# photon_at7020_1.net
KiCad netlist of a schematic drawn in EAGLE
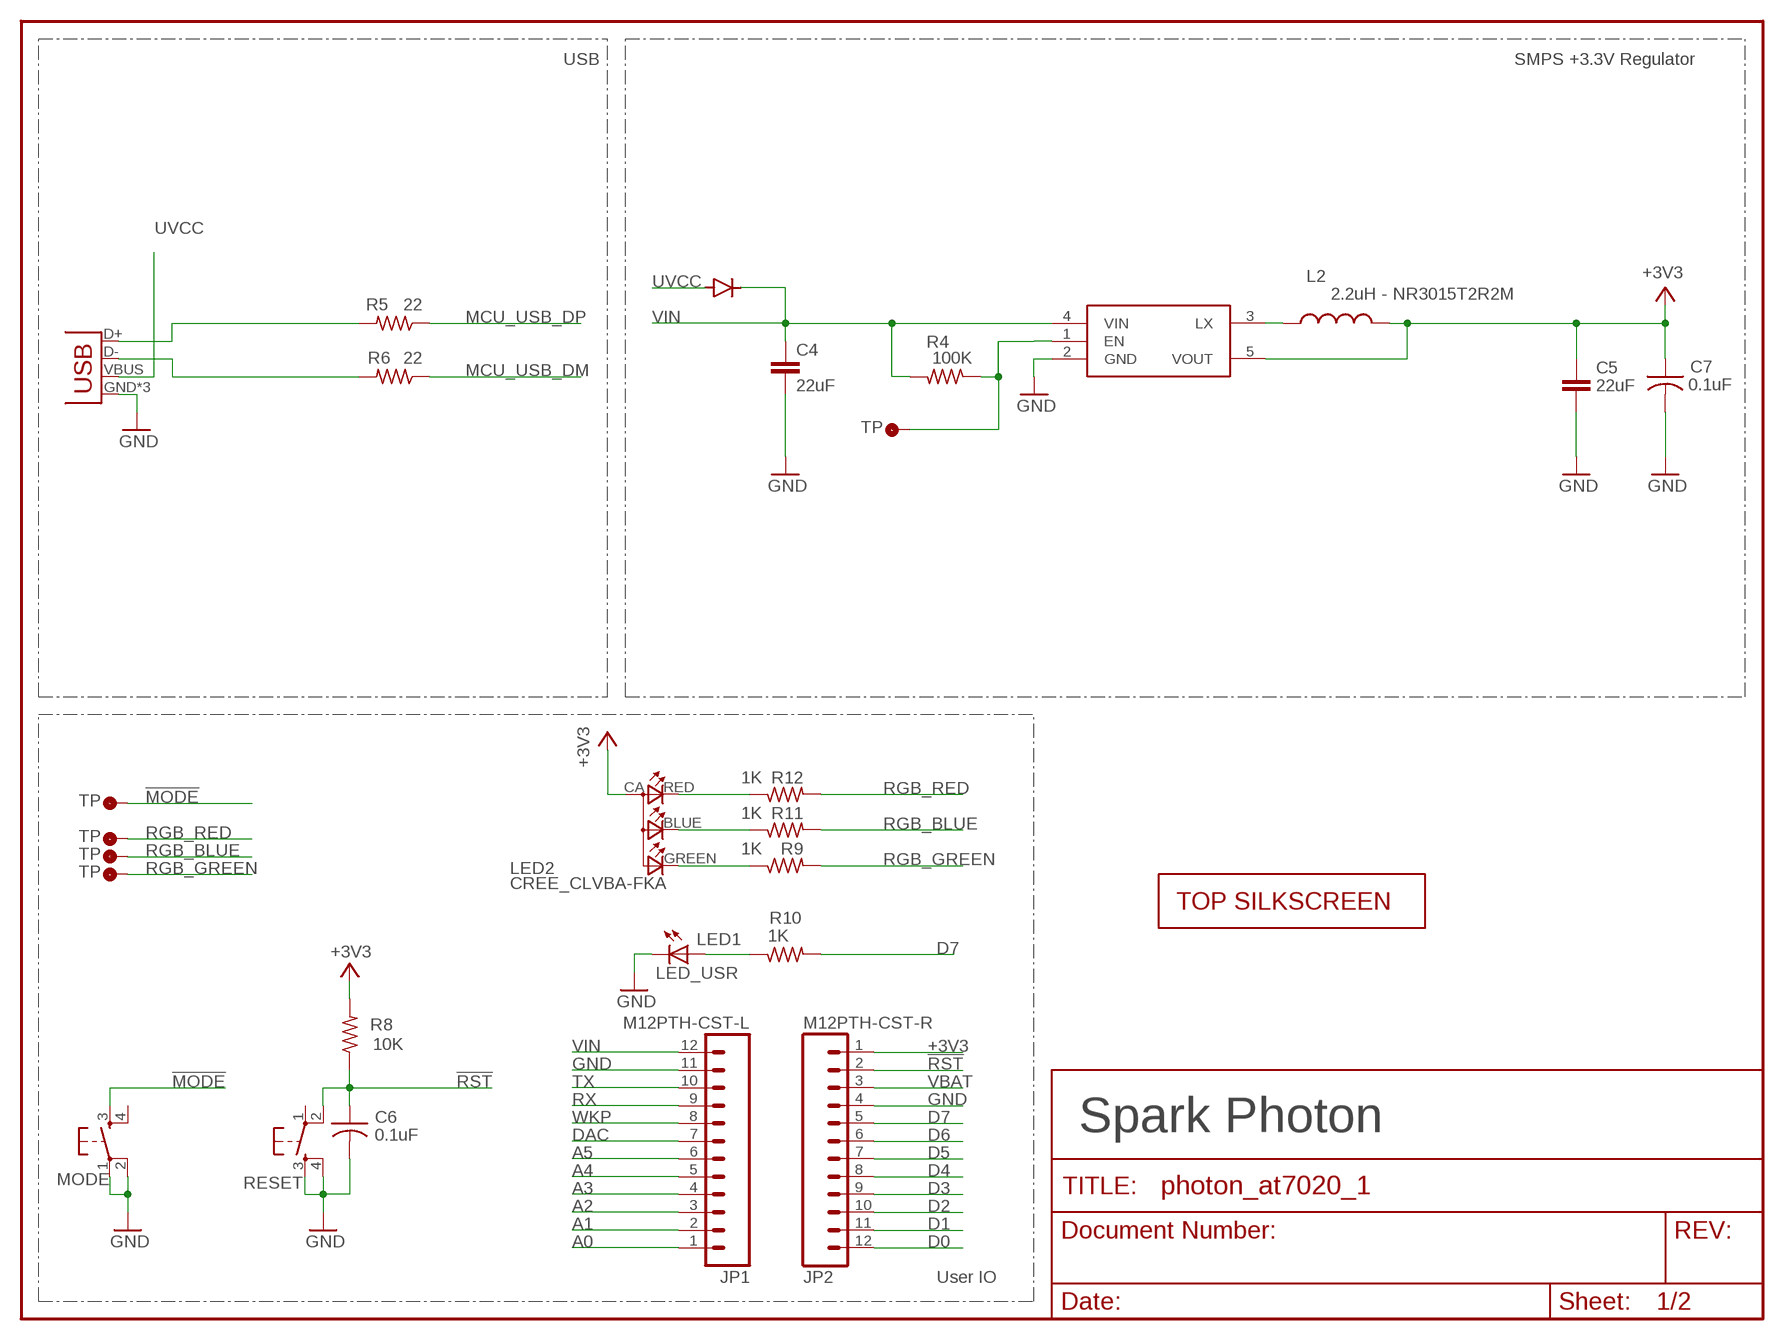
[diagram p0: schematic, sheet 1]
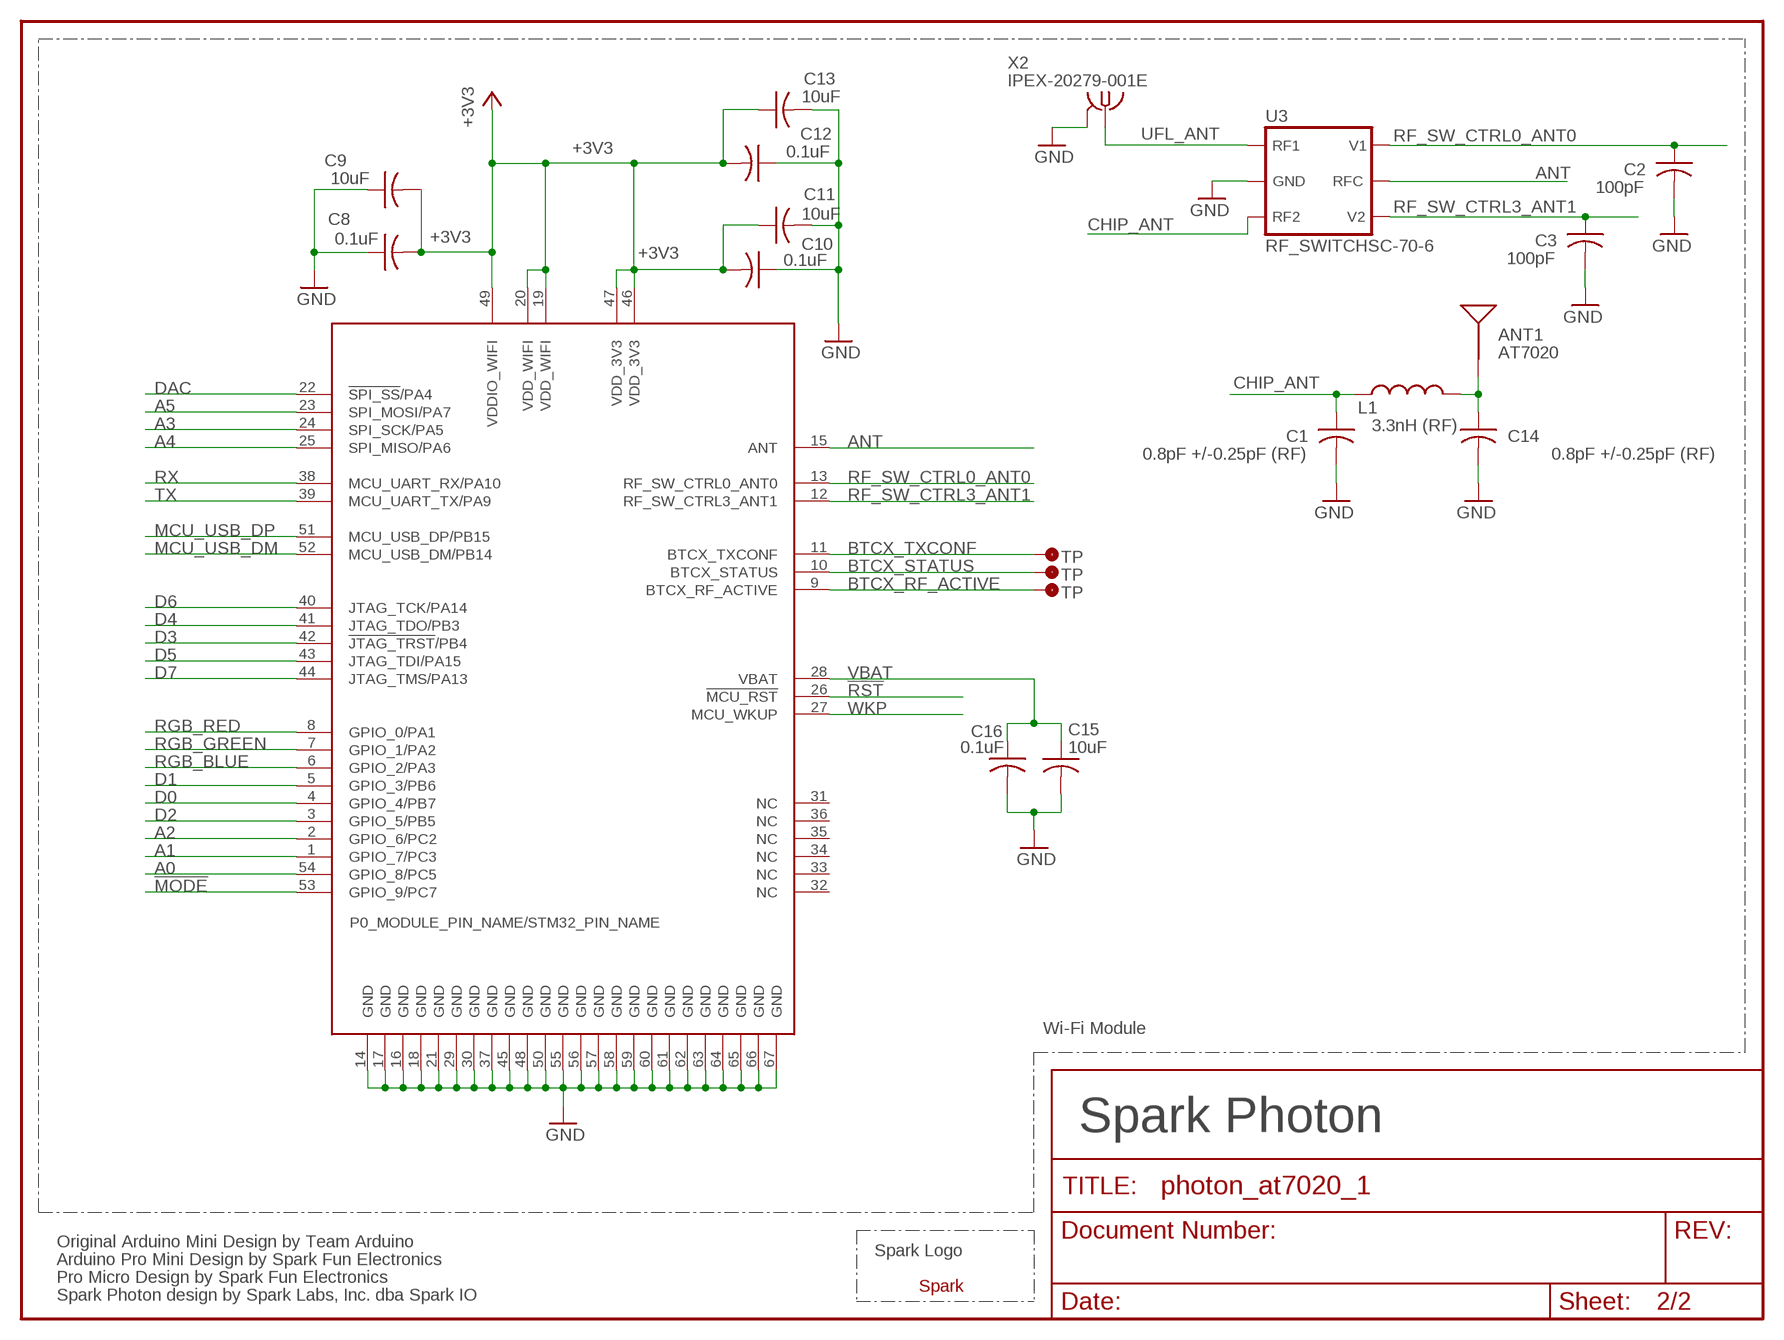
[diagram p1: schematic, sheet 2]

(export (version "E")
  (design (tool "Eeschema 10.0.6"))
  (components
    (comp (ref "C4")
      (value "22uF")
      (footprint "eagle-import:C0603")
      (libsource (lib "eagle-import") (part "C-EUC0603"))
    )
    (comp (ref "C5")
      (value "22uF")
      (footprint "eagle-import:C0603")
      (libsource (lib "eagle-import") (part "C-EUC0603"))
    )
    (comp (ref "C6")
      (value "0.1uF")
      (footprint "eagle-import:C0402_B")
      (libsource (lib "eagle-import") (part "C-US"))
    )
    (comp (ref "C7")
      (value "0.1uF")
      (footprint "eagle-import:C0402")
      (libsource (lib "eagle-import") (part "C-USC0402"))
    )
    (comp (ref "D1")
      (value "DIODE")
      (footprint "eagle-import:DIODE-DO-220AA(SMP)")
      (libsource (lib "eagle-import") (part "DIODE"))
    )
    (comp (ref "JP1")
      (value "M12PTH-CST-L")
      (footprint "eagle-import:1X12-CASTELLATED")
      (libsource (lib "eagle-import") (part "M12PTH-CST-L"))
    )
    (comp (ref "JP2")
      (value "M12PTH-CST-R")
      (footprint "eagle-import:1X12-CASTELLATED")
      (libsource (lib "eagle-import") (part "M12PTH-CST-R"))
    )
    (comp (ref "L2")
      (value "2.2uH - NR3015T2R2M")
      (footprint "eagle-import:INDUCTOR-NR3015")
      (libsource (lib "eagle-import") (part "INDUCTORB"))
    )
    (comp (ref "LED2")
      (value "CREE_CLVBA-FKA")
      (footprint "eagle-import:PLCC4-2MM-RGB")
      (libsource (lib "eagle-import") (part "RGB-LED-CLMVB-FKARGB"))
    )
    (comp (ref "LED_USR")
      (value "LED0603")
      (footprint "eagle-import:LED-0603")
      (libsource (lib "eagle-import") (part "LED0603"))
    )
    (comp (ref "MODE")
      (value "KMR211GLFS")
      (footprint "eagle-import:TACTILE_SWITCH_SMD")
      (libsource (lib "eagle-import") (part "TAC_SWITCHSMD"))
    )
    (comp (ref "R4")
      (value "100K")
      (footprint "eagle-import:R0402_B")
      (libsource (lib "eagle-import") (part "R-US_"))
    )
    (comp (ref "R5")
      (value "22")
      (footprint "eagle-import:R0402_B")
      (libsource (lib "eagle-import") (part "R-US_"))
    )
    (comp (ref "R6")
      (value "22")
      (footprint "eagle-import:R0402_B")
      (libsource (lib "eagle-import") (part "R-US_"))
    )
    (comp (ref "R8")
      (value "10K")
      (footprint "eagle-import:R0402_B")
      (libsource (lib "eagle-import") (part "R-US_"))
    )
    (comp (ref "R9")
      (value "1K")
      (footprint "eagle-import:R0402_B")
      (libsource (lib "eagle-import") (part "R-US_"))
    )
    (comp (ref "R10")
      (value "1K")
      (footprint "eagle-import:R0402_B")
      (libsource (lib "eagle-import") (part "R-US_"))
    )
    (comp (ref "R11")
      (value "1K")
      (footprint "eagle-import:R0402_B")
      (libsource (lib "eagle-import") (part "R-US_"))
    )
    (comp (ref "R12")
      (value "1K")
      (footprint "eagle-import:R0402_B")
      (libsource (lib "eagle-import") (part "R-US_"))
    )
    (comp (ref "RESET")
      (value "KMR211GLFS")
      (footprint "eagle-import:TACTILE_SWITCH_SMD")
      (libsource (lib "eagle-import") (part "TAC_SWITCHSMD"))
    )
    (comp (ref "U$1")
      (value "PHOTON-TOP-SS")
      (footprint "eagle-import:PHOTON-TOP-SS")
      (libsource (lib "eagle-import") (part "PHOTON-TOP-SS"))
    )
    (comp (ref "U$3")
      (value "TP1")
      (footprint "eagle-import:TP35_BOT")
      (libsource (lib "eagle-import") (part "TP1"))
    )
    (comp (ref "U$5")
      (value "TP1")
      (footprint "eagle-import:TP35_BOT")
      (libsource (lib "eagle-import") (part "TP1"))
    )
    (comp (ref "U$6")
      (value "TP1")
      (footprint "eagle-import:TP35_BOT")
      (libsource (lib "eagle-import") (part "TP1"))
    )
    (comp (ref "U$7")
      (value "TP1")
      (footprint "eagle-import:TP35_BOT")
      (libsource (lib "eagle-import") (part "TP1"))
    )
    (comp (ref "U$11")
      (value "R8008-33")
      (footprint "eagle-import:SOT23-5")
      (libsource (lib "eagle-import") (part "R8008-33"))
    )
    (comp (ref "U$12")
      (value "TP1")
      (footprint "eagle-import:TP35_BOT")
      (libsource (lib "eagle-import") (part "TP1"))
    )
    (comp (ref "X1")
      (value "USB-MICROB")
      (footprint "eagle-import:USB-MICROB-SLOT-HOLE")
      (libsource (lib "eagle-import") (part "USBUSB-MICROB-SLOT-HOLE"))
    )
    (comp (ref "ANT1")
      (value "AT7020")
      (footprint "eagle-import:AT7020")
      (libsource (lib "eagle-import") (part "AT7020"))
    )
    (comp (ref "C1")
      (value "0.8pF +/-0.25pF (RF)")
      (footprint "eagle-import:C0402_B")
      (libsource (lib "eagle-import") (part "C-US"))
    )
    (comp (ref "C2")
      (value "100pF")
      (footprint "eagle-import:C0402_B")
      (libsource (lib "eagle-import") (part "C-US"))
    )
    (comp (ref "C3")
      (value "100pF")
      (footprint "eagle-import:C0402_B")
      (libsource (lib "eagle-import") (part "C-US"))
    )
    (comp (ref "C8")
      (value "0.1uF")
      (footprint "eagle-import:C0402_B")
      (libsource (lib "eagle-import") (part "C-US"))
    )
    (comp (ref "C9")
      (value "10uF")
      (footprint "eagle-import:C0402_B")
      (libsource (lib "eagle-import") (part "C-US"))
    )
    (comp (ref "C10")
      (value "0.1uF")
      (footprint "eagle-import:C0402_B")
      (libsource (lib "eagle-import") (part "C-US"))
    )
    (comp (ref "C11")
      (value "10uF")
      (footprint "eagle-import:C0402_B")
      (libsource (lib "eagle-import") (part "C-US"))
    )
    (comp (ref "C12")
      (value "0.1uF")
      (footprint "eagle-import:C0402_B")
      (libsource (lib "eagle-import") (part "C-US"))
    )
    (comp (ref "C13")
      (value "10uF")
      (footprint "eagle-import:C0402_B")
      (libsource (lib "eagle-import") (part "C-US"))
    )
    (comp (ref "C14")
      (value "0.8pF +/-0.25pF (RF)")
      (footprint "eagle-import:C0402_B")
      (libsource (lib "eagle-import") (part "C-US"))
    )
    (comp (ref "C15")
      (value "10uF")
      (footprint "eagle-import:C0402_B")
      (libsource (lib "eagle-import") (part "C-US"))
    )
    (comp (ref "C16")
      (value "0.1uF")
      (footprint "eagle-import:C0402_B")
      (libsource (lib "eagle-import") (part "C-US"))
    )
    (comp (ref "L1")
      (value "3.3nH (RF)")
      (footprint "eagle-import:L0402_B")
      (libsource (lib "eagle-import") (part "INDUCTOR"))
    )
    (comp (ref "U$2")
      (value "SPARK_LOGO2")
      (footprint "eagle-import:SPARK_LOGO2")
      (libsource (lib "eagle-import") (part "SPARK_LOGO2"))
    )
    (comp (ref "U$8")
      (value "TP1")
      (footprint "eagle-import:TP35_BOT")
      (libsource (lib "eagle-import") (part "TP1"))
    )
    (comp (ref "U$9")
      (value "TP1")
      (footprint "eagle-import:TP35_BOT")
      (libsource (lib "eagle-import") (part "TP1"))
    )
    (comp (ref "U$10")
      (value "TP1")
      (footprint "eagle-import:TP35_BOT")
      (libsource (lib "eagle-import") (part "TP1"))
    )
    (comp (ref "U1")
      (value "WM-N-BM-09")
      (footprint "eagle-import:WM-N-BM-09")
      (libsource (lib "eagle-import") (part "WM-N-BM-09"))
    )
    (comp (ref "U3")
      (value "RF_SWITCHSC-70-6")
      (footprint "eagle-import:SC70-6")
      (libsource (lib "eagle-import") (part "RF_SWITCHSC-70-6"))
    )
    (comp (ref "X2")
      (value "IPEX-20279-001E")
      (footprint "eagle-import:IPEX-20279-001E")
      (libsource (lib "eagle-import") (part "IPEX-20279-001E"))
    )
  )
  (nets
    (net (code "1") (name "+3V3") (class "Default")
      (node (ref "C10") (pin "2") (pinfunction "2_2") (pintype "passive"))
      (node (ref "C11") (pin "1") (pinfunction "1_1") (pintype "passive"))
      (node (ref "C12") (pin "2") (pinfunction "2_2") (pintype "passive"))
      (node (ref "C13") (pin "1") (pinfunction "1_1") (pintype "passive"))
      (node (ref "C5") (pin "1") (pinfunction "1_1") (pintype "passive"))
      (node (ref "C7") (pin "1") (pinfunction "1_1") (pintype "passive"))
      (node (ref "C8") (pin "2") (pinfunction "2_2") (pintype "passive"))
      (node (ref "C9") (pin "2") (pinfunction "2_2") (pintype "passive"))
      (node (ref "JP2") (pin "1") (pinfunction "1_1") (pintype "passive"))
      (node (ref "L2") (pin "2") (pinfunction "2_2") (pintype "passive"))
      (node (ref "LED2") (pin "CA") (pinfunction "A2_CA") (pintype "passive"))
      (node (ref "R8") (pin "2") (pinfunction "2_2") (pintype "passive"))
      (node (ref "U$11") (pin "5") (pinfunction "VOUT_5") (pintype "bidirectional"))
      (node (ref "U1") (pin "19") (pinfunction "VDD_WIFI_19") (pintype "bidirectional"))
      (node (ref "U1") (pin "20") (pinfunction "VDD_WIFI_20") (pintype "bidirectional"))
      (node (ref "U1") (pin "46") (pinfunction "VDD_3V3_46") (pintype "bidirectional"))
      (node (ref "U1") (pin "47") (pinfunction "VDD_3V3_47") (pintype "bidirectional"))
      (node (ref "U1") (pin "49") (pinfunction "VDDIO_WIFI_49") (pintype "bidirectional"))
    )
    (net (code "2") (name "A0") (class "Default")
      (node (ref "JP1") (pin "1") (pinfunction "12_1") (pintype "passive"))
      (node (ref "U1") (pin "54") (pinfunction "GPIO_8/PC5_54") (pintype "bidirectional"))
    )
    (net (code "3") (name "A1") (class "Default")
      (node (ref "JP1") (pin "2") (pinfunction "11_2") (pintype "passive"))
      (node (ref "U1") (pin "1") (pinfunction "GPIO_7/PC3_1") (pintype "bidirectional"))
    )
    (net (code "4") (name "A2") (class "Default")
      (node (ref "JP1") (pin "3") (pinfunction "10_3") (pintype "passive"))
      (node (ref "U1") (pin "2") (pinfunction "GPIO_6/PC2_2") (pintype "bidirectional"))
    )
    (net (code "5") (name "A3") (class "Default")
      (node (ref "JP1") (pin "4") (pinfunction "9_4") (pintype "passive"))
      (node (ref "U1") (pin "24") (pinfunction "SPI_SCK/PA5_24") (pintype "bidirectional"))
    )
    (net (code "6") (name "A4") (class "Default")
      (node (ref "JP1") (pin "5") (pinfunction "8_5") (pintype "passive"))
      (node (ref "U1") (pin "25") (pinfunction "SPI_MISO/PA6_25") (pintype "bidirectional"))
    )
    (net (code "7") (name "A5") (class "Default")
      (node (ref "JP1") (pin "6") (pinfunction "7_6") (pintype "passive"))
      (node (ref "U1") (pin "23") (pinfunction "SPI_MOSI/PA7_23") (pintype "bidirectional"))
    )
    (net (code "8") (name "ANT") (class "Default")
      (node (ref "U1") (pin "15") (pinfunction "ANT_15") (pintype "bidirectional"))
      (node (ref "U3") (pin "5") (pinfunction "RFC_5") (pintype "input"))
    )
    (net (code "9") (name "BTCX_RF_ACTIVE") (class "Default")
      (node (ref "U$10") (pin "P$1") (pinfunction "TP_P$1") (pintype "bidirectional"))
      (node (ref "U1") (pin "9") (pinfunction "BTCX_RF_ACTIVE_9") (pintype "bidirectional"))
    )
    (net (code "10") (name "BTCX_STATUS") (class "Default")
      (node (ref "U$9") (pin "P$1") (pinfunction "TP_P$1") (pintype "bidirectional"))
      (node (ref "U1") (pin "10") (pinfunction "BTCX_STATUS_10") (pintype "bidirectional"))
    )
    (net (code "11") (name "BTCX_TXCONF") (class "Default")
      (node (ref "U$8") (pin "P$1") (pinfunction "TP_P$1") (pintype "bidirectional"))
      (node (ref "U1") (pin "11") (pinfunction "BTCX_TXCONF_11") (pintype "bidirectional"))
    )
    (net (code "12") (name "CHIP_ANT") (class "Default")
      (node (ref "C1") (pin "1") (pinfunction "1_1") (pintype "passive"))
      (node (ref "L1") (pin "1") (pinfunction "1_1") (pintype "passive"))
      (node (ref "U3") (pin "3") (pinfunction "RF2_3") (pintype "output"))
    )
    (net (code "13") (name "D0") (class "Default")
      (node (ref "JP2") (pin "12") (pinfunction "12_12") (pintype "passive"))
      (node (ref "U1") (pin "4") (pinfunction "GPIO_4/PB7_4") (pintype "bidirectional"))
    )
    (net (code "14") (name "D1") (class "Default")
      (node (ref "JP2") (pin "11") (pinfunction "11_11") (pintype "passive"))
      (node (ref "U1") (pin "5") (pinfunction "GPIO_3/PB6_5") (pintype "bidirectional"))
    )
    (net (code "15") (name "D2") (class "Default")
      (node (ref "JP2") (pin "10") (pinfunction "10_10") (pintype "passive"))
      (node (ref "U1") (pin "3") (pinfunction "GPIO_5/PB5_3") (pintype "bidirectional"))
    )
    (net (code "16") (name "D3") (class "Default")
      (node (ref "JP2") (pin "9") (pinfunction "9_9") (pintype "passive"))
      (node (ref "U1") (pin "42") (pinfunction "~{JTAG_TRST}/PB4_42") (pintype "bidirectional"))
    )
    (net (code "17") (name "D4") (class "Default")
      (node (ref "JP2") (pin "8") (pinfunction "8_8") (pintype "passive"))
      (node (ref "U1") (pin "41") (pinfunction "JTAG_TDO/PB3_41") (pintype "bidirectional"))
    )
    (net (code "18") (name "D5") (class "Default")
      (node (ref "JP2") (pin "7") (pinfunction "7_7") (pintype "passive"))
      (node (ref "U1") (pin "43") (pinfunction "JTAG_TDI/PA15_43") (pintype "bidirectional"))
    )
    (net (code "19") (name "D6") (class "Default")
      (node (ref "JP2") (pin "6") (pinfunction "6_6") (pintype "passive"))
      (node (ref "U1") (pin "40") (pinfunction "JTAG_TCK/PA14_40") (pintype "bidirectional"))
    )
    (net (code "20") (name "D7") (class "Default")
      (node (ref "JP2") (pin "5") (pinfunction "5_5") (pintype "passive"))
      (node (ref "R10") (pin "2") (pinfunction "2_2") (pintype "passive"))
      (node (ref "U1") (pin "44") (pinfunction "JTAG_TMS/PA13_44") (pintype "bidirectional"))
    )
    (net (code "21") (name "DAC") (class "Default")
      (node (ref "JP1") (pin "7") (pinfunction "6_7") (pintype "passive"))
      (node (ref "U1") (pin "22") (pinfunction "~{SPI_SS}/PA4_22") (pintype "bidirectional"))
    )
    (net (code "22") (name "GND") (class "Default")
      (node (ref "C1") (pin "2") (pinfunction "2_2") (pintype "passive"))
      (node (ref "C10") (pin "1") (pinfunction "1_1") (pintype "passive"))
      (node (ref "C11") (pin "2") (pinfunction "2_2") (pintype "passive"))
      (node (ref "C12") (pin "1") (pinfunction "1_1") (pintype "passive"))
      (node (ref "C13") (pin "2") (pinfunction "2_2") (pintype "passive"))
      (node (ref "C14") (pin "2") (pinfunction "2_2") (pintype "passive"))
      (node (ref "C15") (pin "2") (pinfunction "2_2") (pintype "passive"))
      (node (ref "C16") (pin "2") (pinfunction "2_2") (pintype "passive"))
      (node (ref "C2") (pin "2") (pinfunction "2_2") (pintype "passive"))
      (node (ref "C3") (pin "2") (pinfunction "2_2") (pintype "passive"))
      (node (ref "C4") (pin "2") (pinfunction "2_2") (pintype "passive"))
      (node (ref "C5") (pin "2") (pinfunction "2_2") (pintype "passive"))
      (node (ref "C6") (pin "2") (pinfunction "2_2") (pintype "passive"))
      (node (ref "C7") (pin "2") (pinfunction "2_2") (pintype "passive"))
      (node (ref "C8") (pin "1") (pinfunction "1_1") (pintype "passive"))
      (node (ref "C9") (pin "1") (pinfunction "1_1") (pintype "passive"))
      (node (ref "JP1") (pin "11") (pinfunction "2_11") (pintype "passive"))
      (node (ref "JP2") (pin "4") (pinfunction "4_4") (pintype "passive"))
      (node (ref "LED_USR") (pin "C") (pinfunction "C_C") (pintype "passive"))
      (node (ref "MODE") (pin "1") (pinfunction "1_1") (pintype "passive"))
      (node (ref "MODE") (pin "2") (pinfunction "2_2") (pintype "passive"))
      (node (ref "RESET") (pin "3") (pinfunction "3_3") (pintype "passive"))
      (node (ref "RESET") (pin "4") (pinfunction "4_4") (pintype "passive"))
      (node (ref "U$11") (pin "2") (pinfunction "GND_2") (pintype "bidirectional"))
      (node (ref "U1") (pin "14") (pinfunction "GND_14") (pintype "bidirectional"))
      (node (ref "U1") (pin "16") (pinfunction "GND_16") (pintype "bidirectional"))
      (node (ref "U1") (pin "17") (pinfunction "GND_17") (pintype "bidirectional"))
      (node (ref "U1") (pin "18") (pinfunction "GND_18") (pintype "bidirectional"))
      (node (ref "U1") (pin "21") (pinfunction "GND_21") (pintype "bidirectional"))
      (node (ref "U1") (pin "29") (pinfunction "GND_29") (pintype "bidirectional"))
      (node (ref "U1") (pin "30") (pinfunction "GND_30") (pintype "bidirectional"))
      (node (ref "U1") (pin "37") (pinfunction "GND_37") (pintype "bidirectional"))
      (node (ref "U1") (pin "45") (pinfunction "GND_45") (pintype "bidirectional"))
      (node (ref "U1") (pin "48") (pinfunction "GND_48") (pintype "bidirectional"))
      (node (ref "U1") (pin "50") (pinfunction "GND_50") (pintype "bidirectional"))
      (node (ref "U1") (pin "55") (pinfunction "GND_55") (pintype "bidirectional"))
      (node (ref "U1") (pin "56") (pinfunction "GND_56") (pintype "bidirectional"))
      (node (ref "U1") (pin "57") (pinfunction "GND_57") (pintype "bidirectional"))
      (node (ref "U1") (pin "58") (pinfunction "GND_58") (pintype "bidirectional"))
      (node (ref "U1") (pin "59") (pinfunction "GND_59") (pintype "bidirectional"))
      (node (ref "U1") (pin "60") (pinfunction "GND_60") (pintype "bidirectional"))
      (node (ref "U1") (pin "61") (pinfunction "GND_61") (pintype "bidirectional"))
      (node (ref "U1") (pin "62") (pinfunction "GND_62") (pintype "bidirectional"))
      (node (ref "U1") (pin "63") (pinfunction "GND_63") (pintype "bidirectional"))
      (node (ref "U1") (pin "64") (pinfunction "GND_64") (pintype "bidirectional"))
      (node (ref "U1") (pin "65") (pinfunction "GND_65") (pintype "bidirectional"))
      (node (ref "U1") (pin "66") (pinfunction "GND_66") (pintype "bidirectional"))
      (node (ref "U1") (pin "67") (pinfunction "GND_67") (pintype "bidirectional"))
      (node (ref "U3") (pin "2") (pinfunction "GND_2") (pintype "power_in"))
      (node (ref "X1") (pin "GND") (pinfunction "GND_GND") (pintype "bidirectional"))
      (node (ref "X1") (pin "MT1") (pinfunction "GND_MT1") (pintype "bidirectional"))
      (node (ref "X1") (pin "MT2") (pinfunction "GND_MT2") (pintype "bidirectional"))
      (node (ref "X2") (pin "2@1") (pinfunction "GND_2@1") (pintype "passive"))
      (node (ref "X2") (pin "2@2") (pinfunction "GND_2@2") (pintype "passive"))
    )
    (net (code "23") (name "LED1") (class "Default")
      (node (ref "LED_USR") (pin "A") (pinfunction "A_A") (pintype "passive"))
      (node (ref "R10") (pin "1") (pinfunction "1_1") (pintype "passive"))
    )
    (net (code "24") (name "MCU_USB_DM") (class "Default")
      (node (ref "R6") (pin "1") (pinfunction "1_1") (pintype "passive"))
      (node (ref "U1") (pin "52") (pinfunction "MCU_USB_DM/PB14_52") (pintype "bidirectional"))
    )
    (net (code "25") (name "MCU_USB_DP") (class "Default")
      (node (ref "R5") (pin "1") (pinfunction "1_1") (pintype "passive"))
      (node (ref "U1") (pin "51") (pinfunction "MCU_USB_DP/PB15_51") (pintype "bidirectional"))
    )
    (net (code "26") (name "Net-(ANT1-SIGNAL)") (class "Default")
      (node (ref "ANT1") (pin "1") (pinfunction "SIGNAL_1") (pintype "bidirectional"))
      (node (ref "C14") (pin "1") (pinfunction "1_1") (pintype "passive"))
      (node (ref "L1") (pin "2") (pinfunction "2_2") (pintype "passive"))
    )
    (net (code "27") (name "Net-(LED2-CBLUE)") (class "Default")
      (node (ref "LED2") (pin "BLUE") (pinfunction "CBLUE_BLUE") (pintype "passive"))
      (node (ref "R11") (pin "1") (pinfunction "1_1") (pintype "passive"))
    )
    (net (code "28") (name "Net-(LED2-CGREEN)") (class "Default")
      (node (ref "LED2") (pin "GREEN") (pinfunction "CGREEN_GREEN") (pintype "passive"))
      (node (ref "R9") (pin "1") (pinfunction "1_1") (pintype "passive"))
    )
    (net (code "29") (name "Net-(LED2-CRED)") (class "Default")
      (node (ref "LED2") (pin "RED") (pinfunction "CRED_RED") (pintype "passive"))
      (node (ref "R12") (pin "1") (pinfunction "1_1") (pintype "passive"))
    )
    (net (code "30") (name "Net-(R5-Pad2)") (class "Default")
      (node (ref "R5") (pin "2") (pinfunction "2_2") (pintype "passive"))
      (node (ref "X1") (pin "D+") (pinfunction "D+_D+") (pintype "bidirectional"))
    )
    (net (code "31") (name "Net-(R6-Pad2)") (class "Default")
      (node (ref "R6") (pin "2") (pinfunction "2_2") (pintype "passive"))
      (node (ref "X1") (pin "D-") (pinfunction "D-_D-") (pintype "bidirectional"))
    )
    (net (code "32") (name "Net-(U$11-EN)") (class "Default")
      (node (ref "R4") (pin "1") (pinfunction "1_1") (pintype "passive"))
      (node (ref "U$11") (pin "1") (pinfunction "EN_1") (pintype "bidirectional"))
      (node (ref "U$12") (pin "P$1") (pinfunction "TP_P$1") (pintype "bidirectional"))
    )
    (net (code "33") (name "Net-(U$11-LX)") (class "Default")
      (node (ref "L2") (pin "1") (pinfunction "1_1") (pintype "passive"))
      (node (ref "U$11") (pin "3") (pinfunction "LX_3") (pintype "bidirectional"))
    )
    (net (code "34") (name "RF_SW_CTRL0_ANT0") (class "Default")
      (node (ref "C2") (pin "1") (pinfunction "1_1") (pintype "passive"))
      (node (ref "U1") (pin "13") (pinfunction "RF_SW_CTRL0_ANT0_13") (pintype "bidirectional"))
      (node (ref "U3") (pin "6") (pinfunction "V1_6") (pintype "input"))
    )
    (net (code "35") (name "RF_SW_CTRL3_ANT1") (class "Default")
      (node (ref "C3") (pin "1") (pinfunction "1_1") (pintype "passive"))
      (node (ref "U1") (pin "12") (pinfunction "RF_SW_CTRL3_ANT1_12") (pintype "bidirectional"))
      (node (ref "U3") (pin "4") (pinfunction "V2_4") (pintype "input"))
    )
    (net (code "36") (name "RGB_BLUE") (class "Default")
      (node (ref "R11") (pin "2") (pinfunction "2_2") (pintype "passive"))
      (node (ref "U$6") (pin "P$1") (pinfunction "TP_P$1") (pintype "bidirectional"))
      (node (ref "U1") (pin "6") (pinfunction "GPIO_2/PA3_6") (pintype "bidirectional"))
    )
    (net (code "37") (name "RGB_GREEN") (class "Default")
      (node (ref "R9") (pin "2") (pinfunction "2_2") (pintype "passive"))
      (node (ref "U$7") (pin "P$1") (pinfunction "TP_P$1") (pintype "bidirectional"))
      (node (ref "U1") (pin "7") (pinfunction "GPIO_1/PA2_7") (pintype "bidirectional"))
    )
    (net (code "38") (name "RGB_RED") (class "Default")
      (node (ref "R12") (pin "2") (pinfunction "2_2") (pintype "passive"))
      (node (ref "U$5") (pin "P$1") (pinfunction "TP_P$1") (pintype "bidirectional"))
      (node (ref "U1") (pin "8") (pinfunction "GPIO_0/PA1_8") (pintype "bidirectional"))
    )
    (net (code "39") (name "RX") (class "Default")
      (node (ref "JP1") (pin "9") (pinfunction "4_9") (pintype "passive"))
      (node (ref "U1") (pin "38") (pinfunction "MCU_UART_RX/PA10_38") (pintype "bidirectional"))
    )
    (net (code "40") (name "TX") (class "Default")
      (node (ref "JP1") (pin "10") (pinfunction "3_10") (pintype "passive"))
      (node (ref "U1") (pin "39") (pinfunction "MCU_UART_TX/PA9_39") (pintype "bidirectional"))
    )
    (net (code "41") (name "UFL_ANT") (class "Default")
      (node (ref "U3") (pin "1") (pinfunction "RF1_1") (pintype "output"))
      (node (ref "X2") (pin "1") (pinfunction "1_1") (pintype "passive"))
    )
    (net (code "42") (name "UVCC") (class "Default")
      (node (ref "D1") (pin "ANODE") (pinfunction "ANODE_ANODE") (pintype "bidirectional"))
      (node (ref "X1") (pin "VBUS") (pinfunction "VBUS_VBUS") (pintype "bidirectional"))
    )
    (net (code "43") (name "VBAT") (class "Default")
      (node (ref "C15") (pin "1") (pinfunction "1_1") (pintype "passive"))
      (node (ref "C16") (pin "1") (pinfunction "1_1") (pintype "passive"))
      (node (ref "JP2") (pin "3") (pinfunction "3_3") (pintype "passive"))
      (node (ref "U1") (pin "28") (pinfunction "VBAT_28") (pintype "bidirectional"))
    )
    (net (code "44") (name "VIN") (class "Default")
      (node (ref "C4") (pin "1") (pinfunction "1_1") (pintype "passive"))
      (node (ref "D1") (pin "CATHODE") (pinfunction "CATHODE_CATHODE") (pintype "bidirectional"))
      (node (ref "JP1") (pin "12") (pinfunction "1_12") (pintype "passive"))
      (node (ref "R4") (pin "2") (pinfunction "2_2") (pintype "passive"))
      (node (ref "U$11") (pin "4") (pinfunction "VIN_4") (pintype "bidirectional"))
    )
    (net (code "45") (name "WKP") (class "Default")
      (node (ref "JP1") (pin "8") (pinfunction "5_8") (pintype "passive"))
      (node (ref "U1") (pin "27") (pinfunction "MCU_WKUP_27") (pintype "bidirectional"))
    )
    (net (code "46") (name "unconnected-(MODE-Pad4)") (class "Default")
      (node (ref "MODE") (pin "4") (pinfunction "4_4") (pintype "passive"))
    )
    (net (code "47") (name "unconnected-(RESET-Pad1)") (class "Default")
      (node (ref "RESET") (pin "1") (pinfunction "1_1") (pintype "passive"))
    )
    (net (code "48") (name "unconnected-(U1-NC-Pad31)") (class "Default")
      (node (ref "U1") (pin "31") (pinfunction "NC_31") (pintype "bidirectional"))
    )
    (net (code "49") (name "unconnected-(U1-NC-Pad32)") (class "Default")
      (node (ref "U1") (pin "32") (pinfunction "NC_32") (pintype "bidirectional"))
    )
    (net (code "50") (name "unconnected-(U1-NC-Pad33)") (class "Default")
      (node (ref "U1") (pin "33") (pinfunction "NC_33") (pintype "bidirectional"))
    )
    (net (code "51") (name "unconnected-(U1-NC-Pad34)") (class "Default")
      (node (ref "U1") (pin "34") (pinfunction "NC_34") (pintype "bidirectional"))
    )
    (net (code "52") (name "unconnected-(U1-NC-Pad35)") (class "Default")
      (node (ref "U1") (pin "35") (pinfunction "NC_35") (pintype "bidirectional"))
    )
    (net (code "53") (name "unconnected-(U1-NC-Pad36)") (class "Default")
      (node (ref "U1") (pin "36") (pinfunction "NC_36") (pintype "bidirectional"))
    )
    (net (code "54") (name "~{MODE}") (class "Default")
      (node (ref "MODE") (pin "3") (pinfunction "3_3") (pintype "passive"))
      (node (ref "U$3") (pin "P$1") (pinfunction "TP_P$1") (pintype "bidirectional"))
      (node (ref "U1") (pin "53") (pinfunction "GPIO_9/PC7_53") (pintype "bidirectional"))
    )
    (net (code "55") (name "~{RST}") (class "Default")
      (node (ref "C6") (pin "1") (pinfunction "1_1") (pintype "passive"))
      (node (ref "JP2") (pin "2") (pinfunction "2_2") (pintype "passive"))
      (node (ref "R8") (pin "1") (pinfunction "1_1") (pintype "passive"))
      (node (ref "RESET") (pin "2") (pinfunction "2_2") (pintype "passive"))
      (node (ref "U1") (pin "26") (pinfunction "~{MCU_RST}_26") (pintype "bidirectional"))
    )
  )
)
